# ZYNQ_DDR3.net
KiCad netlist of a schematic drawn in Altium Designer
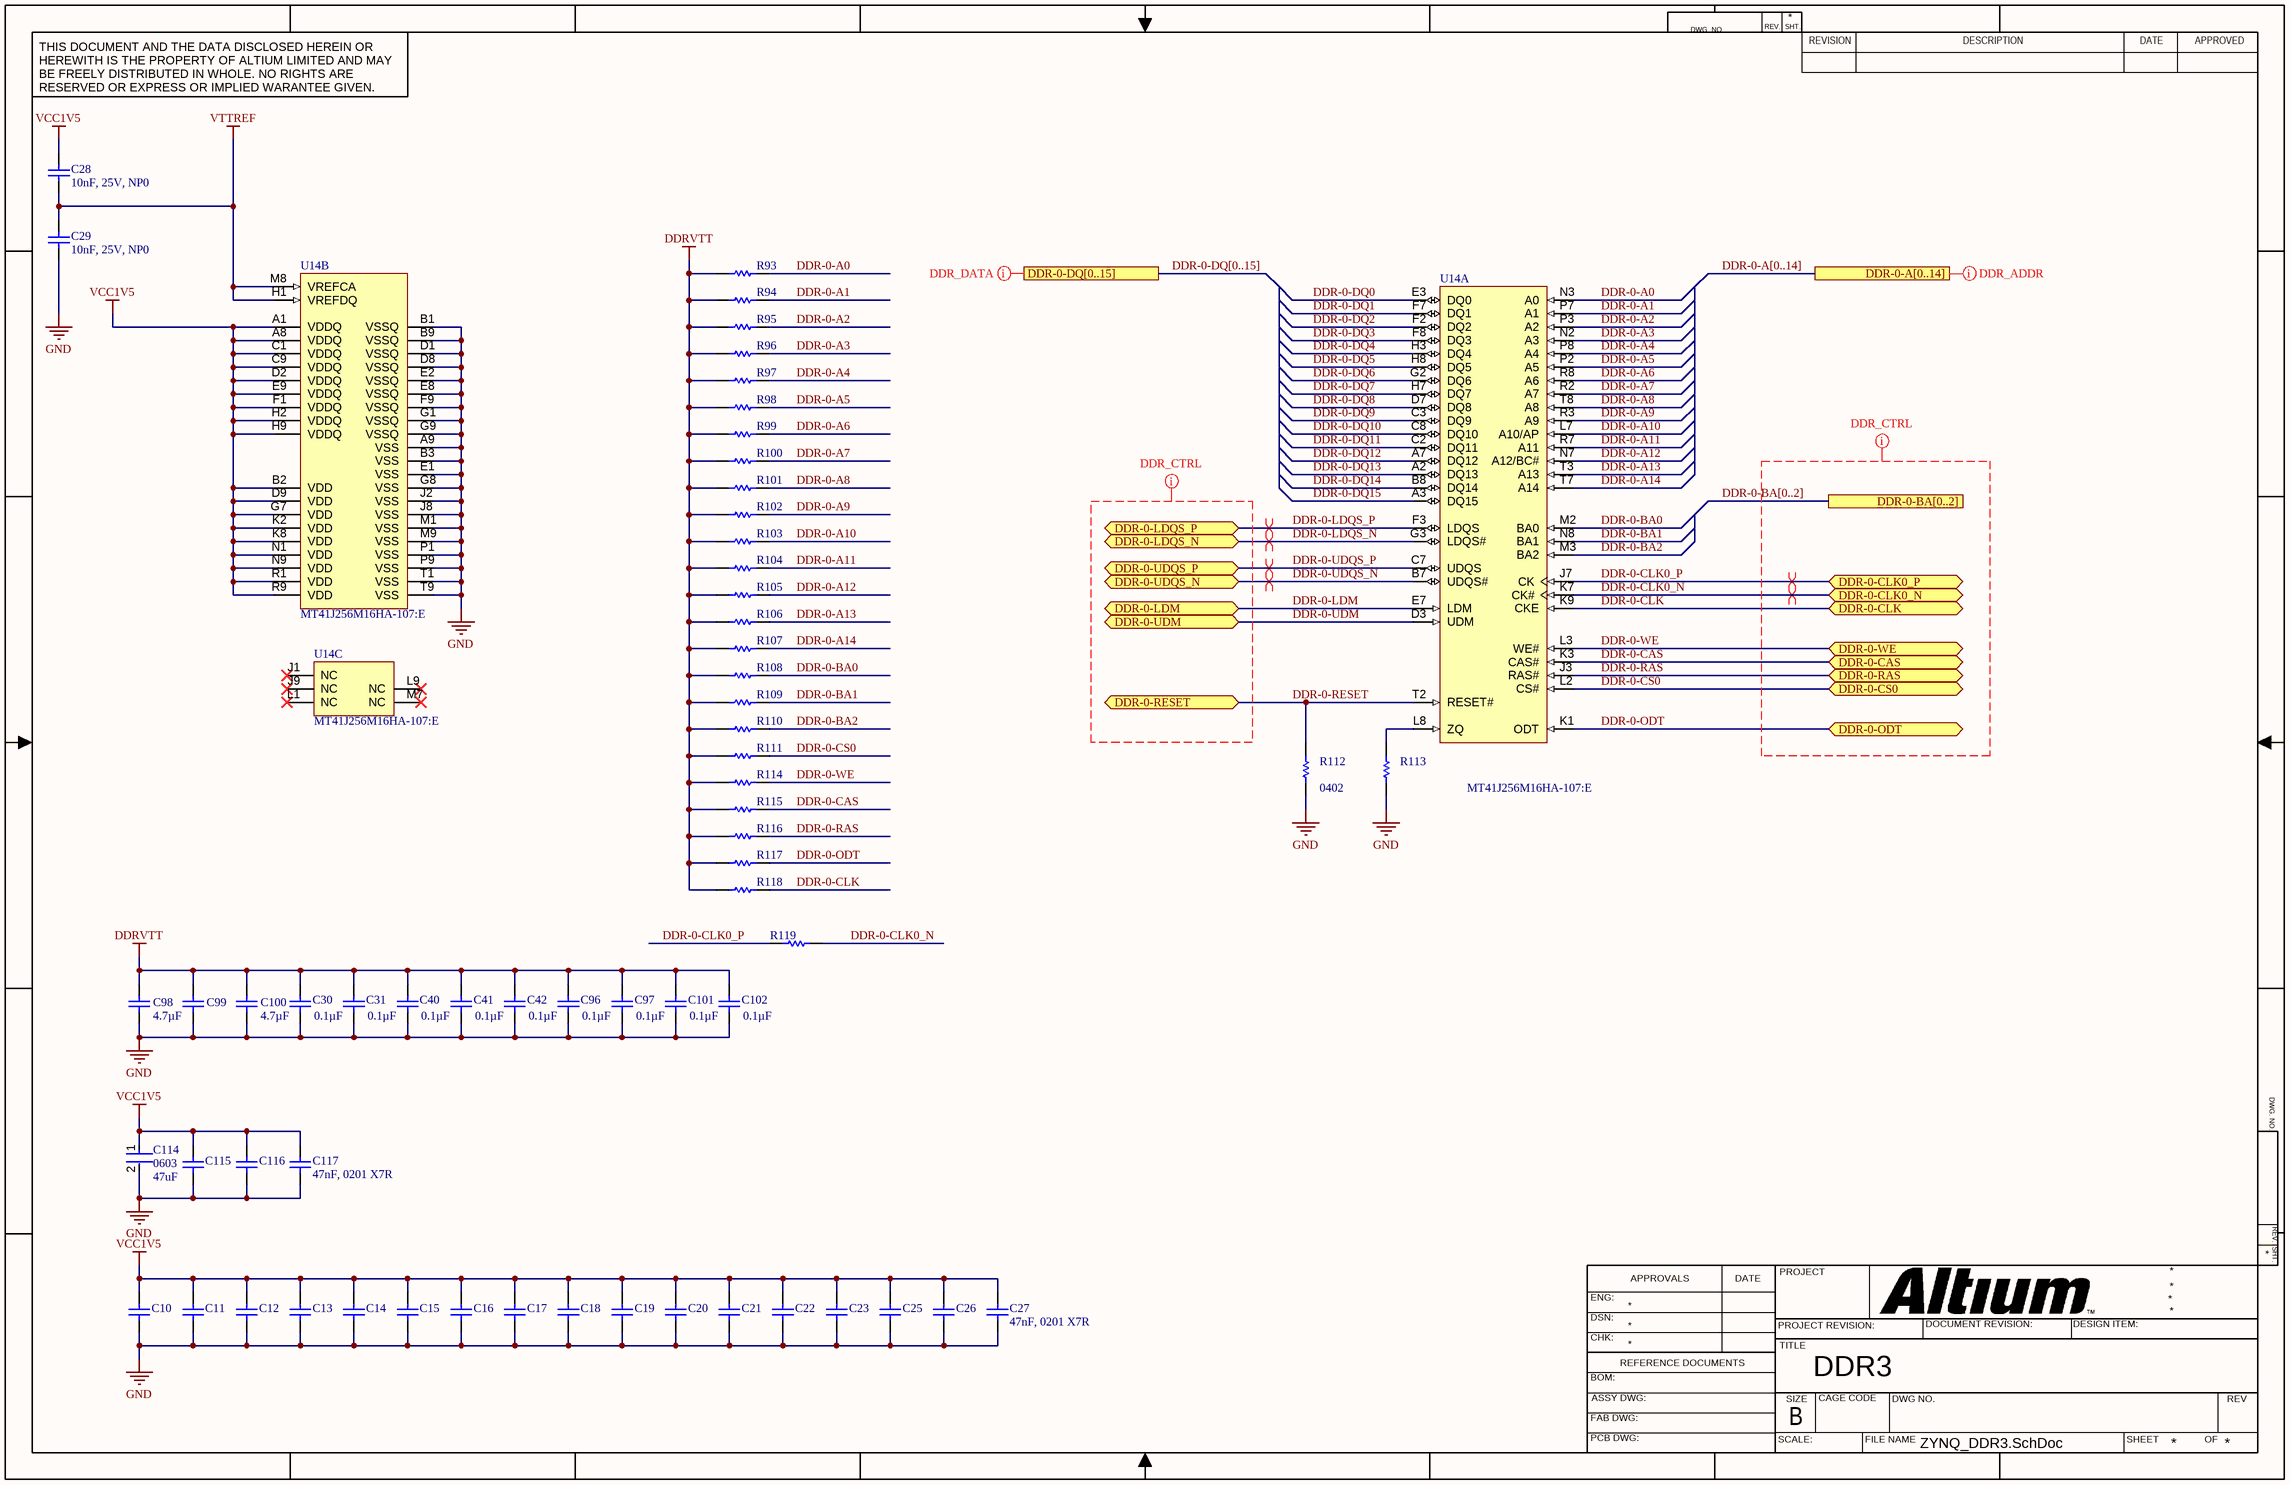
[diagram p0: ZYNQ_DDR3.SchDoc]

(export (version "E")
  (design (tool "Eeschema 10.0.6"))
  (components
    (comp (ref "C10")
      (value "~")
      (footprint "CAP0201i")
      (description "0201, 47nF, 10%, 25V, X7R")
      (libsource (lib "AmpherLib") (part "Cap_47nF_X7R_0201"))
    )
    (comp (ref "C11")
      (value "~")
      (footprint "CAP0201i")
      (description "0201, 47nF, 10%, 25V, X7R")
      (libsource (lib "AmpherLib") (part "Cap_47nF_X7R_0201"))
    )
    (comp (ref "C12")
      (value "~")
      (footprint "CAP0201i")
      (description "0201, 47nF, 10%, 25V, X7R")
      (libsource (lib "AmpherLib") (part "Cap_47nF_X7R_0201"))
    )
    (comp (ref "C13")
      (value "~")
      (footprint "CAP0201i")
      (description "0201, 47nF, 10%, 25V, X7R")
      (libsource (lib "AmpherLib") (part "Cap_47nF_X7R_0201"))
    )
    (comp (ref "C14")
      (value "~")
      (footprint "CAP0201i")
      (description "0201, 47nF, 10%, 25V, X7R")
      (libsource (lib "AmpherLib") (part "Cap_47nF_X7R_0201"))
    )
    (comp (ref "C15")
      (value "~")
      (footprint "CAP0201i")
      (description "0201, 47nF, 10%, 25V, X7R")
      (libsource (lib "AmpherLib") (part "Cap_47nF_X7R_0201"))
    )
    (comp (ref "C16")
      (value "~")
      (footprint "CAP0201i")
      (description "0201, 47nF, 10%, 25V, X7R")
      (libsource (lib "AmpherLib") (part "Cap_47nF_X7R_0201"))
    )
    (comp (ref "C17")
      (value "~")
      (footprint "CAP0201i")
      (description "0201, 47nF, 10%, 25V, X7R")
      (libsource (lib "AmpherLib") (part "Cap_47nF_X7R_0201"))
    )
    (comp (ref "C18")
      (value "~")
      (footprint "CAP0201i")
      (description "0201, 47nF, 10%, 25V, X7R")
      (libsource (lib "AmpherLib") (part "Cap_47nF_X7R_0201"))
    )
    (comp (ref "C19")
      (value "~")
      (footprint "CAP0201i")
      (description "0201, 47nF, 10%, 25V, X7R")
      (libsource (lib "AmpherLib") (part "Cap_47nF_X7R_0201"))
    )
    (comp (ref "C20")
      (value "~")
      (footprint "CAP0201i")
      (description "0201, 47nF, 10%, 25V, X7R")
      (libsource (lib "AmpherLib") (part "Cap_47nF_X7R_0201"))
    )
    (comp (ref "C21")
      (value "~")
      (footprint "CAP0201i")
      (description "0201, 47nF, 10%, 25V, X7R")
      (libsource (lib "AmpherLib") (part "Cap_47nF_X7R_0201"))
    )
    (comp (ref "C22")
      (value "~")
      (footprint "CAP0201i")
      (description "0201, 47nF, 10%, 25V, X7R")
      (libsource (lib "AmpherLib") (part "Cap_47nF_X7R_0201"))
    )
    (comp (ref "C23")
      (value "~")
      (footprint "CAP0201i")
      (description "0201, 47nF, 10%, 25V, X7R")
      (libsource (lib "AmpherLib") (part "Cap_47nF_X7R_0201"))
    )
    (comp (ref "C25")
      (value "~")
      (footprint "CAP0201i")
      (description "0201, 47nF, 10%, 25V, X7R")
      (libsource (lib "AmpherLib") (part "Cap_47nF_X7R_0201"))
    )
    (comp (ref "C26")
      (value "~")
      (footprint "CAP0201i")
      (description "0201, 47nF, 10%, 25V, X7R")
      (libsource (lib "AmpherLib") (part "Cap_47nF_X7R_0201"))
    )
    (comp (ref "C27")
      (value "47nF, 0201 X7R")
      (footprint "CAP0201i")
      (description "0201, 47nF, 10%, 25V, X7R")
      (libsource (lib "AmpherLib") (part "Cap_47nF_X7R_0201"))
    )
    (comp (ref "C28")
      (value "10nF, 25V, NP0")
      (footprint "CAP0402i")
      (description "0402,10nF,5%,25V,NP0")
      (fields (field (name "PART NUMBER") "GRM1555C1E103JE01J") (field (name "MANUFACTURER") "Murata"))
      (libsource (lib "AmpherLib") (part "Cap_10nF_25V_NP0_0402"))
    )
    (comp (ref "C29")
      (value "10nF, 25V, NP0")
      (footprint "CAP0402i")
      (description "0402,10nF,5%,25V,NP0")
      (fields (field (name "PART NUMBER") "GRM1555C1E103JE01J") (field (name "MANUFACTURER") "Murata"))
      (libsource (lib "AmpherLib") (part "Cap_10nF_25V_NP0_0402"))
    )
    (comp (ref "C30")
      (value "0.1µF")
      (footprint "CAP0402i")
      (description "0402, 0.1uF, 10%,  50V, X7R")
      (fields
        (field (name "PART NUMBER") "C1005X7R1H104K050BE")
        (field (name "VOLTAGE") "50V")
        (field (name "CAPACITANCE") "0.1µF")
      )
      (libsource (lib "AmpherLib") (part "Cap_0.1uF_50V_X7R_0402"))
    )
    (comp (ref "C31")
      (value "0.1µF")
      (footprint "CAP0402i")
      (description "0402, 0.1uF, 10%,  50V, X7R")
      (fields
        (field (name "PART NUMBER") "C1005X7R1H104K050BE")
        (field (name "VOLTAGE") "50V")
        (field (name "CAPACITANCE") "0.1µF")
      )
      (libsource (lib "AmpherLib") (part "Cap_0.1uF_50V_X7R_0402"))
    )
    (comp (ref "C40")
      (value "0.1µF")
      (footprint "CAP0402i")
      (description "0402, 0.1uF, 10%,  50V, X7R")
      (fields
        (field (name "PART NUMBER") "C1005X7R1H104K050BE")
        (field (name "VOLTAGE") "50V")
        (field (name "CAPACITANCE") "0.1µF")
      )
      (libsource (lib "AmpherLib") (part "Cap_0.1uF_50V_X7R_0402"))
    )
    (comp (ref "C41")
      (value "0.1µF")
      (footprint "CAP0402i")
      (description "0402, 0.1uF, 10%,  50V, X7R")
      (fields
        (field (name "PART NUMBER") "C1005X7R1H104K050BE")
        (field (name "VOLTAGE") "50V")
        (field (name "CAPACITANCE") "0.1µF")
      )
      (libsource (lib "AmpherLib") (part "Cap_0.1uF_50V_X7R_0402"))
    )
    (comp (ref "C42")
      (value "0.1µF")
      (footprint "CAP0402i")
      (description "0402, 0.1uF, 10%,  50V, X7R")
      (fields
        (field (name "PART NUMBER") "C1005X7R1H104K050BE")
        (field (name "VOLTAGE") "50V")
        (field (name "CAPACITANCE") "0.1µF")
      )
      (libsource (lib "AmpherLib") (part "Cap_0.1uF_50V_X7R_0402"))
    )
    (comp (ref "C96")
      (value "0.1µF")
      (footprint "CAP0402i")
      (description "0402, 0.1uF, 10%,  50V, X7R")
      (fields
        (field (name "PART NUMBER") "C1005X7R1H104K050BE")
        (field (name "VOLTAGE") "50V")
        (field (name "CAPACITANCE") "0.1µF")
      )
      (libsource (lib "AmpherLib") (part "Cap_0.1uF_50V_X7R_0402"))
    )
    (comp (ref "C97")
      (value "0.1µF")
      (footprint "CAP0402i")
      (description "0402, 0.1uF, 10%,  50V, X7R")
      (fields
        (field (name "PART NUMBER") "C1005X7R1H104K050BE")
        (field (name "VOLTAGE") "50V")
        (field (name "CAPACITANCE") "0.1µF")
      )
      (libsource (lib "AmpherLib") (part "Cap_0.1uF_50V_X7R_0402"))
    )
    (comp (ref "C98")
      (value "4.7µF")
      (footprint "CAP0402i")
      (description "CAP CER 4.7UF 10V X5R 0402")
      (fields
        (field (name "TOLERANCE") "10%")
        (field (name "CAPACITANCE") "4.7µF")
        (field (name "PART NUMBER") "C1005X5R1A475K050BC")
      )
      (libsource (lib "AmpherLib") (part "Cap_4.7uF_10V_10%_0402"))
    )
    (comp (ref "C99")
      (value "4.7µF")
      (footprint "CAP0402i")
      (description "CAP CER 4.7UF 10V X5R 0402")
      (fields (field (name "TOLERANCE") "10%") (field (name "PART NUMBER") "C1005X5R1A475K050BC"))
      (libsource (lib "AmpherLib") (part "Cap_4.7uF_10V_10%_0402"))
    )
    (comp (ref "C100")
      (value "4.7µF")
      (footprint "CAP0402i")
      (description "CAP CER 4.7UF 10V X5R 0402")
      (fields
        (field (name "TOLERANCE") "10%")
        (field (name "CAPACITANCE") "4.7µF")
        (field (name "PART NUMBER") "C1005X5R1A475K050BC")
      )
      (libsource (lib "AmpherLib") (part "Cap_4.7uF_10V_10%_0402"))
    )
    (comp (ref "C101")
      (value "0.1µF")
      (footprint "CAP0402i")
      (description "0402, 0.1uF, 10%,  50V, X7R")
      (fields
        (field (name "PART NUMBER") "C1005X7R1H104K050BE")
        (field (name "VOLTAGE") "50V")
        (field (name "CAPACITANCE") "0.1µF")
      )
      (libsource (lib "AmpherLib") (part "Cap_0.1uF_50V_X7R_0402"))
    )
    (comp (ref "C102")
      (value "0.1µF")
      (footprint "CAP0402i")
      (description "0402, 0.1uF, 10%,  50V, X7R")
      (fields
        (field (name "PART NUMBER") "C1005X7R1H104K050BE")
        (field (name "VOLTAGE") "50V")
        (field (name "CAPACITANCE") "0.1µF")
      )
      (libsource (lib "AmpherLib") (part "Cap_0.1uF_50V_X7R_0402"))
    )
    (comp (ref "C114")
      (value "GRM188R60J476ME15D")
      (footprint "FP-GRM188-0_2-IPC_B")
      (description "Chip Multilayer Ceramic Capacitors for General Purpose, 0603, 47uF, X5R, 15%, 20%, 6.3V")
      (fields
        (field (name "CASE CODE (IMPERIAL)") "0603")
        (field (name "CAPACITANCE") "47uF")
        (field (name "TOLERANCE") "20%")
      )
      (libsource (lib "Altium Content Vault") (part "11868f565c42a9108669ba33697ecf6"))
    )
    (comp (ref "C115")
      (value "4.7µF")
      (footprint "CAP0402i")
      (description "CAP CER 4.7UF 10V X5R 0402")
      (fields (field (name "TOLERANCE") "10%") (field (name "PART NUMBER") "C1005X5R1A475K050BC"))
      (libsource (lib "AmpherLib") (part "Cap_4.7uF_10V_10%_0402"))
    )
    (comp (ref "C116")
      (value "~")
      (footprint "CAP0201i")
      (description "0201, 47nF, 10%, 25V, X7R")
      (libsource (lib "AmpherLib") (part "Cap_47nF_X7R_0201"))
    )
    (comp (ref "C117")
      (value "47nF, 0201 X7R")
      (footprint "CAP0201i")
      (description "0201, 47nF, 10%, 25V, X7R")
      (libsource (lib "AmpherLib") (part "Cap_47nF_X7R_0201"))
    )
    (comp (ref "R93")
      (value "ERJ2RKF33R0X")
      (footprint "RESC1005X40X25LL05T05")
      (fields (field (name "MANUFACTURER") "Panasonic"))
      (libsource (lib "Altium Content Vault") (part "RES"))
    )
    (comp (ref "R94")
      (value "ERJ2RKF33R0X")
      (footprint "RESC1005X40X25LL05T05")
      (fields (field (name "MANUFACTURER") "Panasonic"))
      (libsource (lib "Altium Content Vault") (part "RES"))
    )
    (comp (ref "R95")
      (value "ERJ2RKF33R0X")
      (footprint "RESC1005X40X25LL05T05")
      (fields (field (name "MANUFACTURER") "Panasonic"))
      (libsource (lib "Altium Content Vault") (part "RES"))
    )
    (comp (ref "R96")
      (value "ERJ2RKF33R0X")
      (footprint "RESC1005X40X25LL05T05")
      (fields (field (name "MANUFACTURER") "Panasonic"))
      (libsource (lib "Altium Content Vault") (part "RES"))
    )
    (comp (ref "R97")
      (value "ERJ2RKF33R0X")
      (footprint "RESC1005X40X25LL05T05")
      (fields (field (name "MANUFACTURER") "Panasonic"))
      (libsource (lib "Altium Content Vault") (part "RES"))
    )
    (comp (ref "R98")
      (value "ERJ2RKF33R0X")
      (footprint "RESC1005X40X25LL05T05")
      (fields (field (name "MANUFACTURER") "Panasonic"))
      (libsource (lib "Altium Content Vault") (part "RES"))
    )
    (comp (ref "R99")
      (value "ERJ2RKF33R0X")
      (footprint "RESC1005X40X25LL05T05")
      (fields (field (name "MANUFACTURER") "Panasonic"))
      (libsource (lib "Altium Content Vault") (part "RES"))
    )
    (comp (ref "R100")
      (value "ERJ2RKF33R0X")
      (footprint "RESC1005X40X25LL05T05")
      (fields (field (name "MANUFACTURER") "Panasonic"))
      (libsource (lib "Altium Content Vault") (part "RES"))
    )
    (comp (ref "R101")
      (value "ERJ2RKF33R0X")
      (footprint "RESC1005X40X25LL05T05")
      (fields (field (name "MANUFACTURER") "Panasonic"))
      (libsource (lib "Altium Content Vault") (part "RES"))
    )
    (comp (ref "R102")
      (value "ERJ2RKF33R0X")
      (footprint "RESC1005X40X25LL05T05")
      (fields (field (name "MANUFACTURER") "Panasonic"))
      (libsource (lib "Altium Content Vault") (part "RES"))
    )
    (comp (ref "R103")
      (value "ERJ2RKF33R0X")
      (footprint "RESC1005X40X25LL05T05")
      (fields (field (name "MANUFACTURER") "Panasonic"))
      (libsource (lib "Altium Content Vault") (part "RES"))
    )
    (comp (ref "R104")
      (value "ERJ2RKF33R0X")
      (footprint "RESC1005X40X25LL05T05")
      (fields (field (name "MANUFACTURER") "Panasonic"))
      (libsource (lib "Altium Content Vault") (part "RES"))
    )
    (comp (ref "R105")
      (value "ERJ2RKF33R0X")
      (footprint "RESC1005X40X25LL05T05")
      (fields (field (name "MANUFACTURER") "Panasonic"))
      (libsource (lib "Altium Content Vault") (part "RES"))
    )
    (comp (ref "R106")
      (value "ERJ2RKF33R0X")
      (footprint "RESC1005X40X25LL05T05")
      (fields (field (name "MANUFACTURER") "Panasonic"))
      (libsource (lib "Altium Content Vault") (part "RES"))
    )
    (comp (ref "R107")
      (value "ERJ2RKF33R0X")
      (footprint "RESC1005X40X25LL05T05")
      (fields (field (name "MANUFACTURER") "Panasonic"))
      (libsource (lib "Altium Content Vault") (part "RES"))
    )
    (comp (ref "R108")
      (value "ERJ2RKF33R0X")
      (footprint "RESC1005X40X25LL05T05")
      (fields (field (name "MANUFACTURER") "Panasonic"))
      (libsource (lib "Altium Content Vault") (part "RES"))
    )
    (comp (ref "R109")
      (value "ERJ2RKF33R0X")
      (footprint "RESC1005X40X25LL05T05")
      (fields (field (name "MANUFACTURER") "Panasonic"))
      (libsource (lib "Altium Content Vault") (part "RES"))
    )
    (comp (ref "R110")
      (value "ERJ2RKF33R0X")
      (footprint "RESC1005X40X25LL05T05")
      (fields (field (name "MANUFACTURER") "Panasonic"))
      (libsource (lib "Altium Content Vault") (part "RES"))
    )
    (comp (ref "R111")
      (value "ERJ2RKF33R0X")
      (footprint "RESC1005X40X25LL05T05")
      (fields (field (name "MANUFACTURER") "Panasonic"))
      (libsource (lib "Altium Content Vault") (part "RES"))
    )
    (comp (ref "R112")
      (value "ERJ-2RKF4701X")
      (footprint "RESC1005X40X25LL05T05")
      (description "Chip Resistor, 4.7 KOhm, +/- 1%, 0.1 W, -55 to 155 degC, 0402 (1005 Metric), RoHS, Tape and Reel")
      (fields (field (name "PACKAGEREFERENCE") "0402") (field (name "TOLERANCE") "1%"))
      (libsource (lib "Altium Content Vault") (part "RES-2"))
    )
    (comp (ref "R113")
      (value "CRCW0402240RFKED")
      (footprint "RESC1005X40X25ML05T05")
      (fields (field (name "MANUFACTURER") "Vishay Dale"))
      (libsource (lib "Altium Content Vault") (part "RES"))
    )
    (comp (ref "R114")
      (value "ERJ2RKF33R0X")
      (footprint "RESC1005X40X25LL05T05")
      (fields (field (name "MANUFACTURER") "Panasonic"))
      (libsource (lib "Altium Content Vault") (part "RES"))
    )
    (comp (ref "R115")
      (value "ERJ2RKF33R0X")
      (footprint "RESC1005X40X25LL05T05")
      (fields (field (name "MANUFACTURER") "Panasonic"))
      (libsource (lib "Altium Content Vault") (part "RES"))
    )
    (comp (ref "R116")
      (value "ERJ2RKF33R0X")
      (footprint "RESC1005X40X25LL05T05")
      (fields (field (name "MANUFACTURER") "Panasonic"))
      (libsource (lib "Altium Content Vault") (part "RES"))
    )
    (comp (ref "R117")
      (value "ERJ2RKF33R0X")
      (footprint "RESC1005X40X25LL05T05")
      (fields (field (name "MANUFACTURER") "Panasonic"))
      (libsource (lib "Altium Content Vault") (part "RES"))
    )
    (comp (ref "R118")
      (value "ERJ2RKF33R0X")
      (footprint "RESC1005X40X25LL05T05")
      (fields (field (name "MANUFACTURER") "Panasonic"))
      (libsource (lib "Altium Content Vault") (part "RES"))
    )
    (comp (ref "R119")
      (value "CRCW040282R0FKED")
      (footprint "RESC1005X40X25NL05T05")
      (fields (field (name "MANUFACTURER") "Vishay Dale"))
      (libsource (lib "Altium Content Vault") (part "RES"))
    )
    (comp (ref "U14")
      (value "MT41J256M16HA-107:E")
      (footprint "MICT-HA-96")
      (description "4Gb DDR3 SDRAM, 256 Meg x 16, 1.5 V, 0 to 95 degC, 96-Ball FBGA (HA), RoHS, Tray")
      (fields (field (name "MANUFACTURER") "Micron"))
      (libsource (lib "") (part "MICT-MT41J256M16HA-96_1"))
    )
  )
  (nets
    (net (code "1") (name "/DDR-0-A0") (class "Default")
      (node (ref "R93") (pin "2") (pinfunction "2_2") (pintype "passive"))
      (node (ref "U14") (pin "N3") (pinfunction "A0_N3") (pintype "input"))
    )
    (net (code "2") (name "/DDR-0-A1") (class "Default")
      (node (ref "R94") (pin "2") (pinfunction "2_2") (pintype "passive"))
      (node (ref "U14") (pin "P7") (pinfunction "A1_P7") (pintype "input"))
    )
    (net (code "3") (name "/DDR-0-A2") (class "Default")
      (node (ref "R95") (pin "2") (pinfunction "2_2") (pintype "passive"))
      (node (ref "U14") (pin "P3") (pinfunction "A2_P3") (pintype "input"))
    )
    (net (code "4") (name "/DDR-0-A3") (class "Default")
      (node (ref "R96") (pin "2") (pinfunction "2_2") (pintype "passive"))
      (node (ref "U14") (pin "N2") (pinfunction "A3_N2") (pintype "input"))
    )
    (net (code "5") (name "/DDR-0-A4") (class "Default")
      (node (ref "R97") (pin "2") (pinfunction "2_2") (pintype "passive"))
      (node (ref "U14") (pin "P8") (pinfunction "A4_P8") (pintype "input"))
    )
    (net (code "6") (name "/DDR-0-A5") (class "Default")
      (node (ref "R98") (pin "2") (pinfunction "2_2") (pintype "passive"))
      (node (ref "U14") (pin "P2") (pinfunction "A5_P2") (pintype "input"))
    )
    (net (code "7") (name "/DDR-0-A6") (class "Default")
      (node (ref "R99") (pin "2") (pinfunction "2_2") (pintype "passive"))
      (node (ref "U14") (pin "R8") (pinfunction "A6_R8") (pintype "input"))
    )
    (net (code "8") (name "/DDR-0-A7") (class "Default")
      (node (ref "R100") (pin "2") (pinfunction "2_2") (pintype "passive"))
      (node (ref "U14") (pin "R2") (pinfunction "A7_R2") (pintype "input"))
    )
    (net (code "9") (name "/DDR-0-A8") (class "Default")
      (node (ref "R101") (pin "2") (pinfunction "2_2") (pintype "passive"))
      (node (ref "U14") (pin "T8") (pinfunction "A8_T8") (pintype "input"))
    )
    (net (code "10") (name "/DDR-0-A9") (class "Default")
      (node (ref "R102") (pin "2") (pinfunction "2_2") (pintype "passive"))
      (node (ref "U14") (pin "R3") (pinfunction "A9_R3") (pintype "input"))
    )
    (net (code "11") (name "/DDR-0-A10") (class "Default")
      (node (ref "R103") (pin "2") (pinfunction "2_2") (pintype "passive"))
      (node (ref "U14") (pin "L7") (pinfunction "A10/AP_L7") (pintype "input"))
    )
    (net (code "12") (name "/DDR-0-A11") (class "Default")
      (node (ref "R104") (pin "2") (pinfunction "2_2") (pintype "passive"))
      (node (ref "U14") (pin "R7") (pinfunction "A11_R7") (pintype "input"))
    )
    (net (code "13") (name "/DDR-0-A12") (class "Default")
      (node (ref "R105") (pin "2") (pinfunction "2_2") (pintype "passive"))
      (node (ref "U14") (pin "N7") (pinfunction "A12/BC#_N7") (pintype "input"))
    )
    (net (code "14") (name "/DDR-0-A13") (class "Default")
      (node (ref "R106") (pin "2") (pinfunction "2_2") (pintype "passive"))
      (node (ref "U14") (pin "T3") (pinfunction "A13_T3") (pintype "input"))
    )
    (net (code "15") (name "/DDR-0-A14") (class "Default")
      (node (ref "R107") (pin "2") (pinfunction "2_2") (pintype "passive"))
      (node (ref "U14") (pin "T7") (pinfunction "A14_T7") (pintype "input"))
    )
    (net (code "17") (name "/DDR-0-BA0") (class "Default")
      (node (ref "R108") (pin "2") (pinfunction "2_2") (pintype "passive"))
      (node (ref "U14") (pin "M2") (pinfunction "BA0_M2") (pintype "input"))
    )
    (net (code "18") (name "/DDR-0-BA1") (class "Default")
      (node (ref "R109") (pin "2") (pinfunction "2_2") (pintype "passive"))
      (node (ref "U14") (pin "N8") (pinfunction "BA1_N8") (pintype "input"))
    )
    (net (code "19") (name "/DDR-0-BA2") (class "Default")
      (node (ref "R110") (pin "2") (pinfunction "2_2") (pintype "passive"))
      (node (ref "U14") (pin "M3") (pinfunction "BA2_M3") (pintype "input"))
    )
    (net (code "21") (name "/DDR-0-CAS") (class "Default")
      (node (ref "R115") (pin "2") (pinfunction "2_2") (pintype "passive"))
      (node (ref "U14") (pin "K3") (pinfunction "CAS#_K3") (pintype "input"))
    )
    (net (code "22") (name "/DDR-0-CLK") (class "Default")
      (node (ref "R118") (pin "2") (pinfunction "2_2") (pintype "passive"))
      (node (ref "U14") (pin "K9") (pinfunction "CKE_K9") (pintype "input"))
    )
    (net (code "23") (name "/DDR-0-CLK0_N") (class "Default")
      (node (ref "R119") (pin "2") (pinfunction "2_2") (pintype "passive"))
      (node (ref "U14") (pin "K7") (pinfunction "CK#_K7") (pintype "input"))
    )
    (net (code "24") (name "/DDR-0-CLK0_P") (class "Default")
      (node (ref "R119") (pin "1") (pinfunction "1_1") (pintype "passive"))
      (node (ref "U14") (pin "J7") (pinfunction "CK_J7") (pintype "input"))
    )
    (net (code "25") (name "/DDR-0-CS0") (class "Default")
      (node (ref "R111") (pin "2") (pinfunction "2_2") (pintype "passive"))
      (node (ref "U14") (pin "L2") (pinfunction "CS#_L2") (pintype "input"))
    )
    (net (code "26") (name "/DDR-0-DQ0") (class "Default")
      (node (ref "U14") (pin "E3") (pinfunction "DQ0_E3") (pintype "bidirectional"))
    )
    (net (code "27") (name "/DDR-0-DQ1") (class "Default")
      (node (ref "U14") (pin "F7") (pinfunction "DQ1_F7") (pintype "bidirectional"))
    )
    (net (code "28") (name "/DDR-0-DQ2") (class "Default")
      (node (ref "U14") (pin "F2") (pinfunction "DQ2_F2") (pintype "bidirectional"))
    )
    (net (code "29") (name "/DDR-0-DQ3") (class "Default")
      (node (ref "U14") (pin "F8") (pinfunction "DQ3_F8") (pintype "bidirectional"))
    )
    (net (code "30") (name "/DDR-0-DQ4") (class "Default")
      (node (ref "U14") (pin "H3") (pinfunction "DQ4_H3") (pintype "bidirectional"))
    )
    (net (code "31") (name "/DDR-0-DQ5") (class "Default")
      (node (ref "U14") (pin "H8") (pinfunction "DQ5_H8") (pintype "bidirectional"))
    )
    (net (code "32") (name "/DDR-0-DQ6") (class "Default")
      (node (ref "U14") (pin "G2") (pinfunction "DQ6_G2") (pintype "bidirectional"))
    )
    (net (code "33") (name "/DDR-0-DQ7") (class "Default")
      (node (ref "U14") (pin "H7") (pinfunction "DQ7_H7") (pintype "bidirectional"))
    )
    (net (code "34") (name "/DDR-0-DQ8") (class "Default")
      (node (ref "U14") (pin "D7") (pinfunction "DQ8_D7") (pintype "bidirectional"))
    )
    (net (code "35") (name "/DDR-0-DQ9") (class "Default")
      (node (ref "U14") (pin "C3") (pinfunction "DQ9_C3") (pintype "bidirectional"))
    )
    (net (code "36") (name "/DDR-0-DQ10") (class "Default")
      (node (ref "U14") (pin "C8") (pinfunction "DQ10_C8") (pintype "bidirectional"))
    )
    (net (code "37") (name "/DDR-0-DQ11") (class "Default")
      (node (ref "U14") (pin "C2") (pinfunction "DQ11_C2") (pintype "bidirectional"))
    )
    (net (code "38") (name "/DDR-0-DQ12") (class "Default")
      (node (ref "U14") (pin "A7") (pinfunction "DQ12_A7") (pintype "bidirectional"))
    )
    (net (code "39") (name "/DDR-0-DQ13") (class "Default")
      (node (ref "U14") (pin "A2") (pinfunction "DQ13_A2") (pintype "bidirectional"))
    )
    (net (code "40") (name "/DDR-0-DQ14") (class "Default")
      (node (ref "U14") (pin "B8") (pinfunction "DQ14_B8") (pintype "bidirectional"))
    )
    (net (code "41") (name "/DDR-0-DQ15") (class "Default")
      (node (ref "U14") (pin "A3") (pinfunction "DQ15_A3") (pintype "bidirectional"))
    )
    (net (code "43") (name "/DDR-0-LDM") (class "Default")
      (node (ref "U14") (pin "E7") (pinfunction "LDM_E7") (pintype "input"))
    )
    (net (code "44") (name "/DDR-0-LDQS_N") (class "Default")
      (node (ref "U14") (pin "G3") (pinfunction "LDQS#_G3") (pintype "bidirectional"))
    )
    (net (code "45") (name "/DDR-0-LDQS_P") (class "Default")
      (node (ref "U14") (pin "F3") (pinfunction "LDQS_F3") (pintype "bidirectional"))
    )
    (net (code "46") (name "/DDR-0-ODT") (class "Default")
      (node (ref "R117") (pin "2") (pinfunction "2_2") (pintype "passive"))
      (node (ref "U14") (pin "K1") (pinfunction "ODT_K1") (pintype "input"))
    )
    (net (code "47") (name "/DDR-0-RAS") (class "Default")
      (node (ref "R116") (pin "2") (pinfunction "2_2") (pintype "passive"))
      (node (ref "U14") (pin "J3") (pinfunction "RAS#_J3") (pintype "input"))
    )
    (net (code "48") (name "/DDR-0-RESET") (class "Default")
      (node (ref "R112") (pin "2") (pinfunction "2_2") (pintype "passive"))
      (node (ref "U14") (pin "T2") (pinfunction "RESET#_T2") (pintype "input"))
    )
    (net (code "49") (name "/DDR-0-UDM") (class "Default")
      (node (ref "U14") (pin "D3") (pinfunction "UDM_D3") (pintype "input"))
    )
    (net (code "50") (name "/DDR-0-UDQS_N") (class "Default")
      (node (ref "U14") (pin "B7") (pinfunction "UDQS#_B7") (pintype "bidirectional"))
    )
    (net (code "51") (name "/DDR-0-UDQS_P") (class "Default")
      (node (ref "U14") (pin "C7") (pinfunction "UDQS_C7") (pintype "bidirectional"))
    )
    (net (code "52") (name "/DDR-0-WE") (class "Default")
      (node (ref "R114") (pin "2") (pinfunction "2_2") (pintype "passive"))
      (node (ref "U14") (pin "L3") (pinfunction "WE#_L3") (pintype "input"))
    )
    (net (code "53") (name "DDRVTT") (class "Default")
      (node (ref "C100") (pin "2") (pinfunction "2_2") (pintype "passive"))
      (node (ref "C101") (pin "2") (pinfunction "2_2") (pintype "passive"))
      (node (ref "C102") (pin "2") (pinfunction "2_2") (pintype "passive"))
      (node (ref "C30") (pin "2") (pinfunction "2_2") (pintype "passive"))
      (node (ref "C31") (pin "2") (pinfunction "2_2") (pintype "passive"))
      (node (ref "C40") (pin "2") (pinfunction "2_2") (pintype "passive"))
      (node (ref "C41") (pin "2") (pinfunction "2_2") (pintype "passive"))
      (node (ref "C42") (pin "2") (pinfunction "2_2") (pintype "passive"))
      (node (ref "C96") (pin "2") (pinfunction "2_2") (pintype "passive"))
      (node (ref "C97") (pin "2") (pinfunction "2_2") (pintype "passive"))
      (node (ref "C98") (pin "2") (pinfunction "2_2") (pintype "passive"))
      (node (ref "C99") (pin "2") (pinfunction "2_2") (pintype "passive"))
      (node (ref "R100") (pin "1") (pinfunction "1_1") (pintype "passive"))
      (node (ref "R101") (pin "1") (pinfunction "1_1") (pintype "passive"))
      (node (ref "R102") (pin "1") (pinfunction "1_1") (pintype "passive"))
      (node (ref "R103") (pin "1") (pinfunction "1_1") (pintype "passive"))
      (node (ref "R104") (pin "1") (pinfunction "1_1") (pintype "passive"))
      (node (ref "R105") (pin "1") (pinfunction "1_1") (pintype "passive"))
      (node (ref "R106") (pin "1") (pinfunction "1_1") (pintype "passive"))
      (node (ref "R107") (pin "1") (pinfunction "1_1") (pintype "passive"))
      (node (ref "R108") (pin "1") (pinfunction "1_1") (pintype "passive"))
      (node (ref "R109") (pin "1") (pinfunction "1_1") (pintype "passive"))
      (node (ref "R110") (pin "1") (pinfunction "1_1") (pintype "passive"))
      (node (ref "R111") (pin "1") (pinfunction "1_1") (pintype "passive"))
      (node (ref "R114") (pin "1") (pinfunction "1_1") (pintype "passive"))
      (node (ref "R115") (pin "1") (pinfunction "1_1") (pintype "passive"))
      (node (ref "R116") (pin "1") (pinfunction "1_1") (pintype "passive"))
      (node (ref "R117") (pin "1") (pinfunction "1_1") (pintype "passive"))
      (node (ref "R118") (pin "1") (pinfunction "1_1") (pintype "passive"))
      (node (ref "R93") (pin "1") (pinfunction "1_1") (pintype "passive"))
      (node (ref "R94") (pin "1") (pinfunction "1_1") (pintype "passive"))
      (node (ref "R95") (pin "1") (pinfunction "1_1") (pintype "passive"))
      (node (ref "R96") (pin "1") (pinfunction "1_1") (pintype "passive"))
      (node (ref "R97") (pin "1") (pinfunction "1_1") (pintype "passive"))
      (node (ref "R98") (pin "1") (pinfunction "1_1") (pintype "passive"))
      (node (ref "R99") (pin "1") (pinfunction "1_1") (pintype "passive"))
    )
    (net (code "54") (name "GND") (class "Default")
      (node (ref "C10") (pin "1") (pinfunction "1_1") (pintype "passive"))
      (node (ref "C100") (pin "1") (pinfunction "1_1") (pintype "passive"))
      (node (ref "C101") (pin "1") (pinfunction "1_1") (pintype "passive"))
      (node (ref "C102") (pin "1") (pinfunction "1_1") (pintype "passive"))
      (node (ref "C11") (pin "1") (pinfunction "1_1") (pintype "passive"))
      (node (ref "C114") (pin "2") (pinfunction "2_2") (pintype "passive"))
      (node (ref "C115") (pin "1") (pinfunction "1_1") (pintype "passive"))
      (node (ref "C116") (pin "1") (pinfunction "1_1") (pintype "passive"))
      (node (ref "C117") (pin "2") (pinfunction "2_2") (pintype "passive"))
      (node (ref "C12") (pin "1") (pinfunction "1_1") (pintype "passive"))
      (node (ref "C13") (pin "1") (pinfunction "1_1") (pintype "passive"))
      (node (ref "C14") (pin "1") (pinfunction "1_1") (pintype "passive"))
      (node (ref "C15") (pin "1") (pinfunction "1_1") (pintype "passive"))
      (node (ref "C16") (pin "1") (pinfunction "1_1") (pintype "passive"))
      (node (ref "C17") (pin "1") (pinfunction "1_1") (pintype "passive"))
      (node (ref "C18") (pin "1") (pinfunction "1_1") (pintype "passive"))
      (node (ref "C19") (pin "1") (pinfunction "1_1") (pintype "passive"))
      (node (ref "C20") (pin "1") (pinfunction "1_1") (pintype "passive"))
      (node (ref "C21") (pin "1") (pinfunction "1_1") (pintype "passive"))
      (node (ref "C22") (pin "1") (pinfunction "1_1") (pintype "passive"))
      (node (ref "C23") (pin "1") (pinfunction "1_1") (pintype "passive"))
      (node (ref "C25") (pin "1") (pinfunction "1_1") (pintype "passive"))
      (node (ref "C26") (pin "1") (pinfunction "1_1") (pintype "passive"))
      (node (ref "C27") (pin "1") (pinfunction "1_1") (pintype "passive"))
      (node (ref "C29") (pin "1") (pinfunction "1_1") (pintype "passive"))
      (node (ref "C30") (pin "1") (pinfunction "1_1") (pintype "passive"))
      (node (ref "C31") (pin "1") (pinfunction "1_1") (pintype "passive"))
      (node (ref "C40") (pin "1") (pinfunction "1_1") (pintype "passive"))
      (node (ref "C41") (pin "1") (pinfunction "1_1") (pintype "passive"))
      (node (ref "C42") (pin "1") (pinfunction "1_1") (pintype "passive"))
      (node (ref "C96") (pin "1") (pinfunction "1_1") (pintype "passive"))
      (node (ref "C97") (pin "1") (pinfunction "1_1") (pintype "passive"))
      (node (ref "C98") (pin "1") (pinfunction "1_1") (pintype "passive"))
      (node (ref "C99") (pin "1") (pinfunction "1_1") (pintype "passive"))
      (node (ref "R112") (pin "1") (pinfunction "1_1") (pintype "passive"))
      (node (ref "R113") (pin "1") (pinfunction "1_1") (pintype "passive"))
      (node (ref "U14") (pin "A9") (pinfunction "VSS_A9") (pintype "power_in"))
      (node (ref "U14") (pin "B1") (pinfunction "VSSQ_B1") (pintype "power_in"))
      (node (ref "U14") (pin "B3") (pinfunction "VSS_B3") (pintype "power_in"))
      (node (ref "U14") (pin "B9") (pinfunction "VSSQ_B9") (pintype "power_in"))
      (node (ref "U14") (pin "D1") (pinfunction "VSSQ_D1") (pintype "power_in"))
      (node (ref "U14") (pin "D8") (pinfunction "VSSQ_D8") (pintype "power_in"))
      (node (ref "U14") (pin "E1") (pinfunction "VSS_E1") (pintype "power_in"))
      (node (ref "U14") (pin "E2") (pinfunction "VSSQ_E2") (pintype "power_in"))
      (node (ref "U14") (pin "E8") (pinfunction "VSSQ_E8") (pintype "power_in"))
      (node (ref "U14") (pin "F9") (pinfunction "VSSQ_F9") (pintype "power_in"))
      (node (ref "U14") (pin "G1") (pinfunction "VSSQ_G1") (pintype "power_in"))
      (node (ref "U14") (pin "G8") (pinfunction "VSS_G8") (pintype "power_in"))
      (node (ref "U14") (pin "G9") (pinfunction "VSSQ_G9") (pintype "power_in"))
      (node (ref "U14") (pin "J2") (pinfunction "VSS_J2") (pintype "power_in"))
      (node (ref "U14") (pin "J8") (pinfunction "VSS_J8") (pintype "power_in"))
      (node (ref "U14") (pin "M1") (pinfunction "VSS_M1") (pintype "power_in"))
      (node (ref "U14") (pin "M9") (pinfunction "VSS_M9") (pintype "power_in"))
      (node (ref "U14") (pin "P1") (pinfunction "VSS_P1") (pintype "power_in"))
      (node (ref "U14") (pin "P9") (pinfunction "VSS_P9") (pintype "power_in"))
      (node (ref "U14") (pin "T1") (pinfunction "VSS_T1") (pintype "power_in"))
      (node (ref "U14") (pin "T9") (pinfunction "VSS_T9") (pintype "power_in"))
    )
    (net (code "55") (name "Net-(U14A-ZQ)") (class "Default")
      (node (ref "R113") (pin "2") (pinfunction "2_2") (pintype "passive"))
      (node (ref "U14") (pin "L8") (pinfunction "ZQ_L8") (pintype "input"))
    )
    (net (code "56") (name "VCC1V5") (class "Default")
      (node (ref "C10") (pin "2") (pinfunction "2_2") (pintype "passive"))
      (node (ref "C11") (pin "2") (pinfunction "2_2") (pintype "passive"))
      (node (ref "C114") (pin "1") (pinfunction "1_1") (pintype "passive"))
      (node (ref "C115") (pin "2") (pinfunction "2_2") (pintype "passive"))
      (node (ref "C116") (pin "2") (pinfunction "2_2") (pintype "passive"))
      (node (ref "C117") (pin "1") (pinfunction "1_1") (pintype "passive"))
      (node (ref "C12") (pin "2") (pinfunction "2_2") (pintype "passive"))
      (node (ref "C13") (pin "2") (pinfunction "2_2") (pintype "passive"))
      (node (ref "C14") (pin "2") (pinfunction "2_2") (pintype "passive"))
      (node (ref "C15") (pin "2") (pinfunction "2_2") (pintype "passive"))
      (node (ref "C16") (pin "2") (pinfunction "2_2") (pintype "passive"))
      (node (ref "C17") (pin "2") (pinfunction "2_2") (pintype "passive"))
      (node (ref "C18") (pin "2") (pinfunction "2_2") (pintype "passive"))
      (node (ref "C19") (pin "2") (pinfunction "2_2") (pintype "passive"))
      (node (ref "C20") (pin "2") (pinfunction "2_2") (pintype "passive"))
      (node (ref "C21") (pin "2") (pinfunction "2_2") (pintype "passive"))
      (node (ref "C22") (pin "2") (pinfunction "2_2") (pintype "passive"))
      (node (ref "C23") (pin "2") (pinfunction "2_2") (pintype "passive"))
      (node (ref "C25") (pin "2") (pinfunction "2_2") (pintype "passive"))
      (node (ref "C26") (pin "2") (pinfunction "2_2") (pintype "passive"))
      (node (ref "C27") (pin "2") (pinfunction "2_2") (pintype "passive"))
      (node (ref "C28") (pin "2") (pinfunction "2_2") (pintype "passive"))
      (node (ref "U14") (pin "A1") (pinfunction "VDDQ_A1") (pintype "power_in"))
      (node (ref "U14") (pin "A8") (pinfunction "VDDQ_A8") (pintype "power_in"))
      (node (ref "U14") (pin "B2") (pinfunction "VDD_B2") (pintype "power_in"))
      (node (ref "U14") (pin "C1") (pinfunction "VDDQ_C1") (pintype "power_in"))
      (node (ref "U14") (pin "C9") (pinfunction "VDDQ_C9") (pintype "power_in"))
      (node (ref "U14") (pin "D2") (pinfunction "VDDQ_D2") (pintype "power_in"))
      (node (ref "U14") (pin "D9") (pinfunction "VDD_D9") (pintype "power_in"))
      (node (ref "U14") (pin "E9") (pinfunction "VDDQ_E9") (pintype "power_in"))
      (node (ref "U14") (pin "F1") (pinfunction "VDDQ_F1") (pintype "power_in"))
      (node (ref "U14") (pin "G7") (pinfunction "VDD_G7") (pintype "power_in"))
      (node (ref "U14") (pin "H2") (pinfunction "VDDQ_H2") (pintype "power_in"))
      (node (ref "U14") (pin "H9") (pinfunction "VDDQ_H9") (pintype "power_in"))
      (node (ref "U14") (pin "K2") (pinfunction "VDD_K2") (pintype "power_in"))
      (node (ref "U14") (pin "K8") (pinfunction "VDD_K8") (pintype "power_in"))
      (node (ref "U14") (pin "N1") (pinfunction "VDD_N1") (pintype "power_in"))
      (node (ref "U14") (pin "N9") (pinfunction "VDD_N9") (pintype "power_in"))
      (node (ref "U14") (pin "R1") (pinfunction "VDD_R1") (pintype "power_in"))
      (node (ref "U14") (pin "R9") (pinfunction "VDD_R9") (pintype "power_in"))
    )
    (net (code "57") (name "VTTREF") (class "Default")
      (node (ref "C28") (pin "1") (pinfunction "1_1") (pintype "passive"))
      (node (ref "C29") (pin "2") (pinfunction "2_2") (pintype "passive"))
      (node (ref "U14") (pin "H1") (pinfunction "VREFDQ_H1") (pintype "input"))
      (node (ref "U14") (pin "M8") (pinfunction "VREFCA_M8") (pintype "input"))
    )
    (net (code "58") (name "unconnected-(U14C-NC-PadJ1)") (class "Default")
      (node (ref "U14") (pin "J1") (pinfunction "NC_J1") (pintype "passive+no_connect"))
    )
    (net (code "59") (name "unconnected-(U14C-NC-PadJ9)") (class "Default")
      (node (ref "U14") (pin "J9") (pinfunction "NC_J9") (pintype "passive+no_connect"))
    )
    (net (code "60") (name "unconnected-(U14C-NC-PadL1)") (class "Default")
      (node (ref "U14") (pin "L1") (pinfunction "NC_L1") (pintype "passive+no_connect"))
    )
    (net (code "61") (name "unconnected-(U14C-NC-PadL9)") (class "Default")
      (node (ref "U14") (pin "L9") (pinfunction "NC_L9") (pintype "passive+no_connect"))
    )
    (net (code "62") (name "unconnected-(U14C-NC-PadM7)") (class "Default")
      (node (ref "U14") (pin "M7") (pinfunction "NC_M7") (pintype "passive+no_connect"))
    )
  )
)
